# capsense-soil-sensor.net
KiCad netlist of a schematic drawn in EAGLE
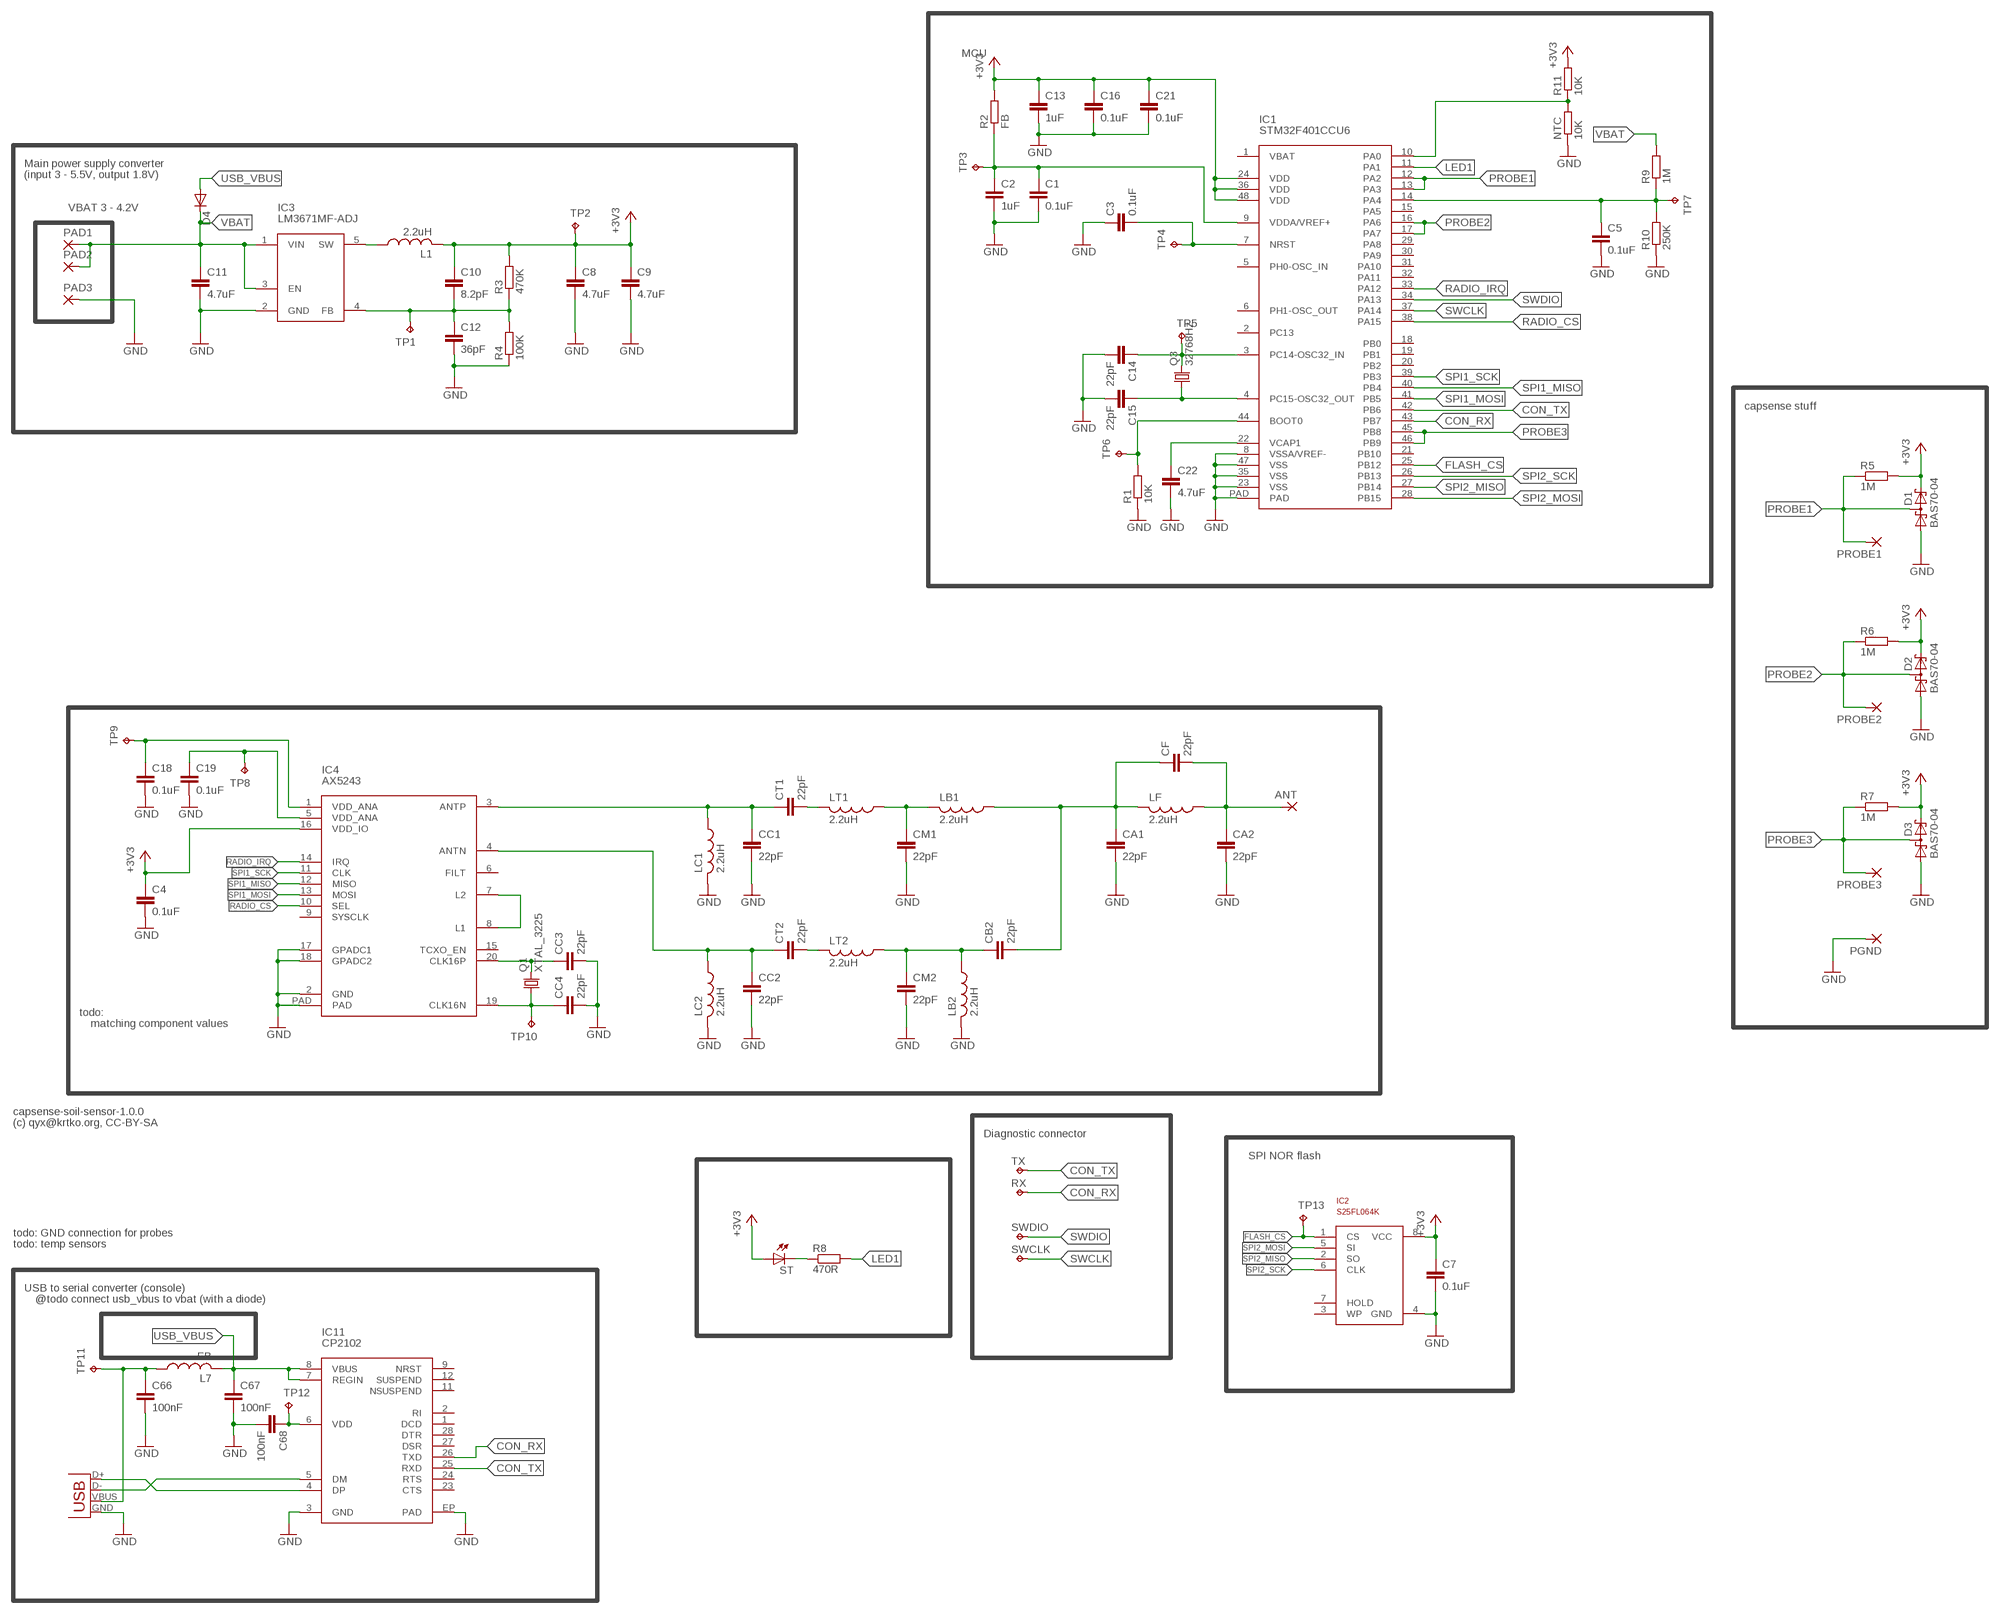
[diagram p0: schematic, sheet 1]

(export (version "E")
  (design (tool "Eeschema 10.0.6"))
  (components
    (comp (ref "ANT")
      (value "2,15/1,0")
      (footprint "eagle-import:2,15_1,0")
      (libsource (lib "eagle-import") (part "2,15/1,0"))
    )
    (comp (ref "C1")
      (value "0.1uF")
      (footprint "eagle-import:C0603")
      (libsource (lib "eagle-import") (part "C-EUC0603"))
    )
    (comp (ref "C2")
      (value "1uF")
      (footprint "eagle-import:C0603")
      (libsource (lib "eagle-import") (part "C-EUC0603"))
    )
    (comp (ref "C3")
      (value "0.1uF")
      (footprint "eagle-import:C0603")
      (libsource (lib "eagle-import") (part "C-EUC0603"))
    )
    (comp (ref "C4")
      (value "0.1uF")
      (footprint "eagle-import:C0603")
      (libsource (lib "eagle-import") (part "C-EUC0603"))
    )
    (comp (ref "C5")
      (value "0.1uF")
      (footprint "eagle-import:C0603")
      (libsource (lib "eagle-import") (part "C-EUC0603"))
    )
    (comp (ref "C7")
      (value "0.1uF")
      (footprint "eagle-import:C0603")
      (libsource (lib "eagle-import") (part "C-EUC0603"))
    )
    (comp (ref "C8")
      (value "4.7uF")
      (footprint "eagle-import:C0805")
      (libsource (lib "eagle-import") (part "C-EUC0805"))
    )
    (comp (ref "C9")
      (value "4.7uF")
      (footprint "eagle-import:C0805")
      (libsource (lib "eagle-import") (part "C-EUC0805"))
    )
    (comp (ref "C10")
      (value "8.2pF")
      (footprint "eagle-import:C0603")
      (libsource (lib "eagle-import") (part "C-EUC0603"))
    )
    (comp (ref "C11")
      (value "4.7uF")
      (footprint "eagle-import:C0805")
      (libsource (lib "eagle-import") (part "C-EUC0805"))
    )
    (comp (ref "C12")
      (value "36pF")
      (footprint "eagle-import:C0603")
      (libsource (lib "eagle-import") (part "C-EUC0603"))
    )
    (comp (ref "C13")
      (value "1uF")
      (footprint "eagle-import:C0603")
      (libsource (lib "eagle-import") (part "C-EUC0603"))
    )
    (comp (ref "C14")
      (value "22pF")
      (footprint "eagle-import:C0603")
      (libsource (lib "eagle-import") (part "C-EUC0603"))
    )
    (comp (ref "C15")
      (value "22pF")
      (footprint "eagle-import:C0603")
      (libsource (lib "eagle-import") (part "C-EUC0603"))
    )
    (comp (ref "C16")
      (value "0.1uF")
      (footprint "eagle-import:C0603")
      (libsource (lib "eagle-import") (part "C-EUC0603"))
    )
    (comp (ref "C18")
      (value "0.1uF")
      (footprint "eagle-import:C0603")
      (libsource (lib "eagle-import") (part "C-EUC0603"))
    )
    (comp (ref "C19")
      (value "0.1uF")
      (footprint "eagle-import:C0603")
      (libsource (lib "eagle-import") (part "C-EUC0603"))
    )
    (comp (ref "C21")
      (value "0.1uF")
      (footprint "eagle-import:C0603")
      (libsource (lib "eagle-import") (part "C-EUC0603"))
    )
    (comp (ref "C22")
      (value "4.7uF")
      (footprint "eagle-import:C0603")
      (libsource (lib "eagle-import") (part "C-EUC0603"))
    )
    (comp (ref "C66")
      (value "100nF")
      (footprint "eagle-import:C0603")
      (libsource (lib "eagle-import") (part "C-EUC0603"))
    )
    (comp (ref "C67")
      (value "100nF")
      (footprint "eagle-import:C0603")
      (libsource (lib "eagle-import") (part "C-EUC0603"))
    )
    (comp (ref "C68")
      (value "100nF")
      (footprint "eagle-import:C0603")
      (libsource (lib "eagle-import") (part "C-EUC0603"))
    )
    (comp (ref "CA1")
      (value "22pF")
      (footprint "eagle-import:C0603")
      (libsource (lib "eagle-import") (part "C-EUC0603"))
    )
    (comp (ref "CA2")
      (value "22pF")
      (footprint "eagle-import:C0603")
      (libsource (lib "eagle-import") (part "C-EUC0603"))
    )
    (comp (ref "CB2")
      (value "22pF")
      (footprint "eagle-import:C0603")
      (libsource (lib "eagle-import") (part "C-EUC0603"))
    )
    (comp (ref "CC1")
      (value "22pF")
      (footprint "eagle-import:C0603")
      (libsource (lib "eagle-import") (part "C-EUC0603"))
    )
    (comp (ref "CC2")
      (value "22pF")
      (footprint "eagle-import:C0603")
      (libsource (lib "eagle-import") (part "C-EUC0603"))
    )
    (comp (ref "CC3")
      (value "22pF")
      (footprint "eagle-import:C0603")
      (libsource (lib "eagle-import") (part "C-EUC0603"))
    )
    (comp (ref "CC4")
      (value "22pF")
      (footprint "eagle-import:C0603")
      (libsource (lib "eagle-import") (part "C-EUC0603"))
    )
    (comp (ref "CF")
      (value "22pF")
      (footprint "eagle-import:C0603")
      (libsource (lib "eagle-import") (part "C-EUC0603"))
    )
    (comp (ref "CM1")
      (value "22pF")
      (footprint "eagle-import:C0603")
      (libsource (lib "eagle-import") (part "C-EUC0603"))
    )
    (comp (ref "CM2")
      (value "22pF")
      (footprint "eagle-import:C0603")
      (libsource (lib "eagle-import") (part "C-EUC0603"))
    )
    (comp (ref "CT1")
      (value "22pF")
      (footprint "eagle-import:C0603")
      (libsource (lib "eagle-import") (part "C-EUC0603"))
    )
    (comp (ref "CT2")
      (value "22pF")
      (footprint "eagle-import:C0603")
      (libsource (lib "eagle-import") (part "C-EUC0603"))
    )
    (comp (ref "D1")
      (value "BAS70-04")
      (footprint "eagle-import:SOT23")
      (libsource (lib "eagle-import") (part "BAS70-04"))
    )
    (comp (ref "D2")
      (value "BAS70-04")
      (footprint "eagle-import:SOT23")
      (libsource (lib "eagle-import") (part "BAS70-04"))
    )
    (comp (ref "D3")
      (value "BAS70-04")
      (footprint "eagle-import:SOT23")
      (libsource (lib "eagle-import") (part "BAS70-04"))
    )
    (comp (ref "D4")
      (value "DIODE-SOD110-R")
      (footprint "eagle-import:SOD110-R")
      (libsource (lib "eagle-import") (part "DIODE-SOD110-R"))
    )
    (comp (ref "IC1")
      (value "STM32F401CCU6")
      (footprint "eagle-import:UFQFPN48")
      (libsource (lib "eagle-import") (part "STM32F401CCU6"))
    )
    (comp (ref "IC2")
      (value "S25FL064K")
      (footprint "eagle-import:SO-08M")
      (libsource (lib "eagle-import") (part "S25FL064K"))
    )
    (comp (ref "IC3")
      (value "LM3671MF-ADJ")
      (footprint "eagle-import:SOT23-5")
      (libsource (lib "eagle-import") (part "LM3671MF"))
    )
    (comp (ref "IC4")
      (value "AX5243")
      (footprint "eagle-import:QFN20")
      (libsource (lib "eagle-import") (part "AX5243"))
    )
    (comp (ref "IC11")
      (value "CP2102")
      (footprint "eagle-import:QFN28")
      (libsource (lib "eagle-import") (part "CP2102"))
    )
    (comp (ref "L1")
      (value "2.2uH")
      (footprint "eagle-import:L2825P")
      (libsource (lib "eagle-import") (part "L-USL2825P"))
    )
    (comp (ref "L7")
      (value "FB")
      (footprint "eagle-import:L2012C")
      (libsource (lib "eagle-import") (part "L-USL2012C"))
    )
    (comp (ref "LB1")
      (value "2.2uH")
      (footprint "eagle-import:L2012C")
      (libsource (lib "eagle-import") (part "L-USL2012C"))
    )
    (comp (ref "LB2")
      (value "2.2uH")
      (footprint "eagle-import:L2012C")
      (libsource (lib "eagle-import") (part "L-USL2012C"))
    )
    (comp (ref "LC1")
      (value "2.2uH")
      (footprint "eagle-import:L2012C")
      (libsource (lib "eagle-import") (part "L-USL2012C"))
    )
    (comp (ref "LC2")
      (value "2.2uH")
      (footprint "eagle-import:L2012C")
      (libsource (lib "eagle-import") (part "L-USL2012C"))
    )
    (comp (ref "LF")
      (value "2.2uH")
      (footprint "eagle-import:L2012C")
      (libsource (lib "eagle-import") (part "L-USL2012C"))
    )
    (comp (ref "LT1")
      (value "2.2uH")
      (footprint "eagle-import:L2012C")
      (libsource (lib "eagle-import") (part "L-USL2012C"))
    )
    (comp (ref "LT2")
      (value "2.2uH")
      (footprint "eagle-import:L2012C")
      (libsource (lib "eagle-import") (part "L-USL2012C"))
    )
    (comp (ref "NTC")
      (value "10K")
      (footprint "eagle-import:R0603")
      (libsource (lib "eagle-import") (part "R-EU_R0603"))
    )
    (comp (ref "PAD1")
      (value "SMD5")
      (footprint "eagle-import:SMD2,54-5,08")
      (libsource (lib "eagle-import") (part "SMD5"))
    )
    (comp (ref "PAD2")
      (value "SMD5")
      (footprint "eagle-import:SMD2,54-5,08")
      (libsource (lib "eagle-import") (part "SMD5"))
    )
    (comp (ref "PAD3")
      (value "2,15/1,0")
      (footprint "eagle-import:2,15_1,0")
      (libsource (lib "eagle-import") (part "2,15/1,0"))
    )
    (comp (ref "PGND")
      (value "2,15/1,0")
      (footprint "eagle-import:2,15_1,0")
      (libsource (lib "eagle-import") (part "2,15/1,0"))
    )
    (comp (ref "PROBE1")
      (value "2,15/1,0")
      (footprint "eagle-import:2,15_1,0")
      (libsource (lib "eagle-import") (part "2,15/1,0"))
    )
    (comp (ref "PROBE2")
      (value "2,15/1,0")
      (footprint "eagle-import:2,15_1,0")
      (libsource (lib "eagle-import") (part "2,15/1,0"))
    )
    (comp (ref "PROBE3")
      (value "2,15/1,0")
      (footprint "eagle-import:2,15_1,0")
      (libsource (lib "eagle-import") (part "2,15/1,0"))
    )
    (comp (ref "Q1")
      (value "XTAL_3225")
      (footprint "eagle-import:XTAL_3225")
      (libsource (lib "eagle-import") (part "XTAL_3225"))
    )
    (comp (ref "Q3")
      (value "32768Hz")
      (footprint "eagle-import:TC26H")
      (libsource (lib "eagle-import") (part "CRYSTALTC26H"))
    )
    (comp (ref "R1")
      (value "10K")
      (footprint "eagle-import:R0603")
      (libsource (lib "eagle-import") (part "R-EU_R0603"))
    )
    (comp (ref "R2")
      (value "FB")
      (footprint "eagle-import:R0603")
      (libsource (lib "eagle-import") (part "R-EU_R0603"))
    )
    (comp (ref "R3")
      (value "470K")
      (footprint "eagle-import:R0603")
      (libsource (lib "eagle-import") (part "R-EU_R0603"))
    )
    (comp (ref "R4")
      (value "100K")
      (footprint "eagle-import:R0603")
      (libsource (lib "eagle-import") (part "R-EU_R0603"))
    )
    (comp (ref "R5")
      (value "1M")
      (footprint "eagle-import:R0603")
      (libsource (lib "eagle-import") (part "R-EU_R0603"))
    )
    (comp (ref "R6")
      (value "1M")
      (footprint "eagle-import:R0603")
      (libsource (lib "eagle-import") (part "R-EU_R0603"))
    )
    (comp (ref "R7")
      (value "1M")
      (footprint "eagle-import:R0603")
      (libsource (lib "eagle-import") (part "R-EU_R0603"))
    )
    (comp (ref "R8")
      (value "470R")
      (footprint "eagle-import:R0603")
      (libsource (lib "eagle-import") (part "R-EU_R0603"))
    )
    (comp (ref "R9")
      (value "1M")
      (footprint "eagle-import:R0603")
      (libsource (lib "eagle-import") (part "R-EU_R0603"))
    )
    (comp (ref "R10")
      (value "250K")
      (footprint "eagle-import:R0603")
      (libsource (lib "eagle-import") (part "R-EU_R0603"))
    )
    (comp (ref "R11")
      (value "10K")
      (footprint "eagle-import:R0603")
      (libsource (lib "eagle-import") (part "R-EU_R0603"))
    )
    (comp (ref "RX")
      (value "TPB2,54")
      (footprint "eagle-import:B2,54")
      (libsource (lib "eagle-import") (part "TPB2,54"))
    )
    (comp (ref "ST")
      (value "LEDCHIPLED_0603")
      (footprint "eagle-import:CHIPLED_0603")
      (libsource (lib "eagle-import") (part "LEDCHIPLED_0603"))
    )
    (comp (ref "SWCLK")
      (value "TPB2,54")
      (footprint "eagle-import:B2,54")
      (libsource (lib "eagle-import") (part "TPB2,54"))
    )
    (comp (ref "SWDIO")
      (value "TPB2,54")
      (footprint "eagle-import:B2,54")
      (libsource (lib "eagle-import") (part "TPB2,54"))
    )
    (comp (ref "TP1")
      (value "TPB1,27")
      (footprint "eagle-import:B1,27")
      (libsource (lib "eagle-import") (part "TPB1,27"))
    )
    (comp (ref "TP2")
      (value "TPB1,27")
      (footprint "eagle-import:B1,27")
      (libsource (lib "eagle-import") (part "TPB1,27"))
    )
    (comp (ref "TP3")
      (value "TPB1,27")
      (footprint "eagle-import:B1,27")
      (libsource (lib "eagle-import") (part "TPB1,27"))
    )
    (comp (ref "TP4")
      (value "TPB1,27")
      (footprint "eagle-import:B1,27")
      (libsource (lib "eagle-import") (part "TPB1,27"))
    )
    (comp (ref "TP5")
      (value "TPB1,27")
      (footprint "eagle-import:B1,27")
      (libsource (lib "eagle-import") (part "TPB1,27"))
    )
    (comp (ref "TP6")
      (value "TPB1,27")
      (footprint "eagle-import:B1,27")
      (libsource (lib "eagle-import") (part "TPB1,27"))
    )
    (comp (ref "TP7")
      (value "TPB1,27")
      (footprint "eagle-import:B1,27")
      (libsource (lib "eagle-import") (part "TPB1,27"))
    )
    (comp (ref "TP8")
      (value "TPB1,27")
      (footprint "eagle-import:B1,27")
      (libsource (lib "eagle-import") (part "TPB1,27"))
    )
    (comp (ref "TP9")
      (value "TPB1,27")
      (footprint "eagle-import:B1,27")
      (libsource (lib "eagle-import") (part "TPB1,27"))
    )
    (comp (ref "TP10")
      (value "TPB1,27")
      (footprint "eagle-import:B1,27")
      (libsource (lib "eagle-import") (part "TPB1,27"))
    )
    (comp (ref "TP11")
      (value "TPB1,27")
      (footprint "eagle-import:B1,27")
      (libsource (lib "eagle-import") (part "TPB1,27"))
    )
    (comp (ref "TP12")
      (value "TPB1,27")
      (footprint "eagle-import:B1,27")
      (libsource (lib "eagle-import") (part "TPB1,27"))
    )
    (comp (ref "TP13")
      (value "TPB1,27")
      (footprint "eagle-import:B1,27")
      (libsource (lib "eagle-import") (part "TPB1,27"))
    )
    (comp (ref "TX")
      (value "TPB2,54")
      (footprint "eagle-import:B2,54")
      (libsource (lib "eagle-import") (part "TPB2,54"))
    )
    (comp (ref "X5")
      (value "USB-MICROB")
      (footprint "eagle-import:USB-MICROB")
      (libsource (lib "eagle-import") (part "USB-MICROB"))
    )
  )
  (nets
    (net (code "1") (name "+3V3") (class "Default")
      (node (ref "C10") (pin "1") (pinfunction "1_1") (pintype "passive"))
      (node (ref "C13") (pin "1") (pinfunction "1_1") (pintype "passive"))
      (node (ref "C16") (pin "1") (pinfunction "1_1") (pintype "passive"))
      (node (ref "C21") (pin "1") (pinfunction "1_1") (pintype "passive"))
      (node (ref "C4") (pin "1") (pinfunction "1_1") (pintype "passive"))
      (node (ref "C7") (pin "1") (pinfunction "1_1") (pintype "passive"))
      (node (ref "C8") (pin "1") (pinfunction "1_1") (pintype "passive"))
      (node (ref "C9") (pin "1") (pinfunction "1_1") (pintype "passive"))
      (node (ref "D1") (pin "2") (pinfunction "C2_2") (pintype "passive"))
      (node (ref "D2") (pin "2") (pinfunction "C2_2") (pintype "passive"))
      (node (ref "D3") (pin "2") (pinfunction "C2_2") (pintype "passive"))
      (node (ref "IC1") (pin "24") (pinfunction "VDD_24") (pintype "bidirectional"))
      (node (ref "IC1") (pin "36") (pinfunction "VDD_36") (pintype "bidirectional"))
      (node (ref "IC1") (pin "48") (pinfunction "VDD_48") (pintype "bidirectional"))
      (node (ref "IC2") (pin "8") (pinfunction "VCC_8") (pintype "power_in"))
      (node (ref "IC4") (pin "16") (pinfunction "VDD_IO_16") (pintype "bidirectional"))
      (node (ref "L1") (pin "2") (pinfunction "2_2") (pintype "passive"))
      (node (ref "R11") (pin "2") (pinfunction "2_2") (pintype "passive"))
      (node (ref "R2") (pin "2") (pinfunction "2_2") (pintype "passive"))
      (node (ref "R3") (pin "2") (pinfunction "2_2") (pintype "passive"))
      (node (ref "R5") (pin "2") (pinfunction "2_2") (pintype "passive"))
      (node (ref "R6") (pin "2") (pinfunction "2_2") (pintype "passive"))
      (node (ref "R7") (pin "2") (pinfunction "2_2") (pintype "passive"))
      (node (ref "ST") (pin "A") (pinfunction "A_A") (pintype "passive"))
      (node (ref "TP2") (pin "TP") (pinfunction "TP_TP") (pintype "input"))
    )
    (net (code "2") (name "CON_RX") (class "Default")
      (node (ref "IC1") (pin "43") (pinfunction "PB7_43") (pintype "bidirectional"))
      (node (ref "IC11") (pin "26") (pinfunction "TXD_26") (pintype "bidirectional"))
      (node (ref "RX") (pin "TP") (pinfunction "TP_TP") (pintype "input"))
    )
    (net (code "3") (name "CON_TX") (class "Default")
      (node (ref "IC1") (pin "42") (pinfunction "PB6_42") (pintype "bidirectional"))
      (node (ref "IC11") (pin "25") (pinfunction "RXD_25") (pintype "bidirectional"))
      (node (ref "TX") (pin "TP") (pinfunction "TP_TP") (pintype "input"))
    )
    (net (code "4") (name "FLASH_CS") (class "Default")
      (node (ref "IC1") (pin "25") (pinfunction "PB12_25") (pintype "bidirectional"))
      (node (ref "IC2") (pin "1") (pinfunction "CS_1") (pintype "bidirectional"))
      (node (ref "TP13") (pin "TP") (pinfunction "TP_TP") (pintype "input"))
    )
    (net (code "5") (name "GND") (class "Default")
      (node (ref "C1") (pin "2") (pinfunction "2_2") (pintype "passive"))
      (node (ref "C11") (pin "2") (pinfunction "2_2") (pintype "passive"))
      (node (ref "C12") (pin "2") (pinfunction "2_2") (pintype "passive"))
      (node (ref "C13") (pin "2") (pinfunction "2_2") (pintype "passive"))
      (node (ref "C14") (pin "2") (pinfunction "2_2") (pintype "passive"))
      (node (ref "C15") (pin "2") (pinfunction "2_2") (pintype "passive"))
      (node (ref "C16") (pin "2") (pinfunction "2_2") (pintype "passive"))
      (node (ref "C18") (pin "2") (pinfunction "2_2") (pintype "passive"))
      (node (ref "C19") (pin "2") (pinfunction "2_2") (pintype "passive"))
      (node (ref "C2") (pin "2") (pinfunction "2_2") (pintype "passive"))
      (node (ref "C21") (pin "2") (pinfunction "2_2") (pintype "passive"))
      (node (ref "C22") (pin "2") (pinfunction "2_2") (pintype "passive"))
      (node (ref "C3") (pin "1") (pinfunction "1_1") (pintype "passive"))
      (node (ref "C4") (pin "2") (pinfunction "2_2") (pintype "passive"))
      (node (ref "C5") (pin "2") (pinfunction "2_2") (pintype "passive"))
      (node (ref "C66") (pin "2") (pinfunction "2_2") (pintype "passive"))
      (node (ref "C67") (pin "2") (pinfunction "2_2") (pintype "passive"))
      (node (ref "C68") (pin "2") (pinfunction "2_2") (pintype "passive"))
      (node (ref "C7") (pin "2") (pinfunction "2_2") (pintype "passive"))
      (node (ref "C8") (pin "2") (pinfunction "2_2") (pintype "passive"))
      (node (ref "C9") (pin "2") (pinfunction "2_2") (pintype "passive"))
      (node (ref "CA1") (pin "2") (pinfunction "2_2") (pintype "passive"))
      (node (ref "CA2") (pin "2") (pinfunction "2_2") (pintype "passive"))
      (node (ref "CC1") (pin "2") (pinfunction "2_2") (pintype "passive"))
      (node (ref "CC2") (pin "2") (pinfunction "2_2") (pintype "passive"))
      (node (ref "CC3") (pin "2") (pinfunction "2_2") (pintype "passive"))
      (node (ref "CC4") (pin "2") (pinfunction "2_2") (pintype "passive"))
      (node (ref "CM1") (pin "2") (pinfunction "2_2") (pintype "passive"))
      (node (ref "CM2") (pin "2") (pinfunction "2_2") (pintype "passive"))
      (node (ref "D1") (pin "1") (pinfunction "A1_1") (pintype "passive"))
      (node (ref "D2") (pin "1") (pinfunction "A1_1") (pintype "passive"))
      (node (ref "D3") (pin "1") (pinfunction "A1_1") (pintype "passive"))
      (node (ref "IC1") (pin "23") (pinfunction "VSS_23") (pintype "bidirectional"))
      (node (ref "IC1") (pin "35") (pinfunction "VSS_35") (pintype "bidirectional"))
      (node (ref "IC1") (pin "47") (pinfunction "VSS_47") (pintype "bidirectional"))
      (node (ref "IC1") (pin "8") (pinfunction "VSSA/VREF-_8") (pintype "bidirectional"))
      (node (ref "IC1") (pin "PAD") (pinfunction "PAD_PAD") (pintype "bidirectional"))
      (node (ref "IC11") (pin "3") (pinfunction "GND_3") (pintype "bidirectional"))
      (node (ref "IC11") (pin "EP") (pinfunction "PAD_EP") (pintype "bidirectional"))
      (node (ref "IC2") (pin "4") (pinfunction "GND_4") (pintype "power_in"))
      (node (ref "IC3") (pin "2") (pinfunction "GND_2") (pintype "bidirectional"))
      (node (ref "IC4") (pin "17") (pinfunction "GPADC1_17") (pintype "bidirectional"))
      (node (ref "IC4") (pin "18") (pinfunction "GPADC2_18") (pintype "bidirectional"))
      (node (ref "IC4") (pin "2") (pinfunction "GND_2") (pintype "bidirectional"))
      (node (ref "IC4") (pin "PAD") (pinfunction "PAD_PAD") (pintype "bidirectional"))
      (node (ref "LB2") (pin "2") (pinfunction "2_2") (pintype "passive"))
      (node (ref "LC1") (pin "2") (pinfunction "2_2") (pintype "passive"))
      (node (ref "LC2") (pin "2") (pinfunction "2_2") (pintype "passive"))
      (node (ref "NTC") (pin "1") (pinfunction "1_1") (pintype "passive"))
      (node (ref "PAD3") (pin "1") (pinfunction "P_1") (pintype "passive"))
      (node (ref "PGND") (pin "1") (pinfunction "P_1") (pintype "passive"))
      (node (ref "R1") (pin "1") (pinfunction "1_1") (pintype "passive"))
      (node (ref "R10") (pin "1") (pinfunction "1_1") (pintype "passive"))
      (node (ref "R4") (pin "1") (pinfunction "1_1") (pintype "passive"))
      (node (ref "X5") (pin "GND") (pinfunction "GND_GND") (pintype "bidirectional"))
    )
    (net (code "6") (name "LED1") (class "Default")
      (node (ref "IC1") (pin "11") (pinfunction "PA1_11") (pintype "bidirectional"))
      (node (ref "R8") (pin "2") (pinfunction "2_2") (pintype "passive"))
    )
    (net (code "7") (name "Net-(ANT-P)") (class "Default")
      (node (ref "ANT") (pin "1") (pinfunction "P_1") (pintype "passive"))
      (node (ref "CA2") (pin "1") (pinfunction "1_1") (pintype "passive"))
      (node (ref "CF") (pin "2") (pinfunction "2_2") (pintype "passive"))
      (node (ref "LF") (pin "1") (pinfunction "1_1") (pintype "passive"))
    )
    (net (code "8") (name "Net-(C18-Pad1)") (class "Default")
      (node (ref "C18") (pin "1") (pinfunction "1_1") (pintype "passive"))
      (node (ref "IC4") (pin "1") (pinfunction "VDD_ANA_1") (pintype "bidirectional"))
      (node (ref "TP9") (pin "TP") (pinfunction "TP_TP") (pintype "input"))
    )
    (net (code "9") (name "Net-(C19-Pad1)") (class "Default")
      (node (ref "C19") (pin "1") (pinfunction "1_1") (pintype "passive"))
      (node (ref "IC4") (pin "5") (pinfunction "VDD_ANA_5") (pintype "bidirectional"))
      (node (ref "TP8") (pin "TP") (pinfunction "TP_TP") (pintype "input"))
    )
    (net (code "10") (name "Net-(C66-Pad1)") (class "Default")
      (node (ref "C66") (pin "1") (pinfunction "1_1") (pintype "passive"))
      (node (ref "L7") (pin "1") (pinfunction "1_1") (pintype "passive"))
      (node (ref "TP11") (pin "TP") (pinfunction "TP_TP") (pintype "input"))
      (node (ref "X5") (pin "VBUS") (pinfunction "VBUS_VBUS") (pintype "bidirectional"))
    )
    (net (code "11") (name "Net-(CA1-Pad1)") (class "Default")
      (node (ref "CA1") (pin "1") (pinfunction "1_1") (pintype "passive"))
      (node (ref "CB2") (pin "2") (pinfunction "2_2") (pintype "passive"))
      (node (ref "CF") (pin "1") (pinfunction "1_1") (pintype "passive"))
      (node (ref "LB1") (pin "1") (pinfunction "1_1") (pintype "passive"))
      (node (ref "LF") (pin "2") (pinfunction "2_2") (pintype "passive"))
    )
    (net (code "12") (name "Net-(CB2-Pad1)") (class "Default")
      (node (ref "CB2") (pin "1") (pinfunction "1_1") (pintype "passive"))
      (node (ref "CM2") (pin "1") (pinfunction "1_1") (pintype "passive"))
      (node (ref "LB2") (pin "1") (pinfunction "1_1") (pintype "passive"))
      (node (ref "LT2") (pin "1") (pinfunction "1_1") (pintype "passive"))
    )
    (net (code "13") (name "Net-(CM1-Pad1)") (class "Default")
      (node (ref "CM1") (pin "1") (pinfunction "1_1") (pintype "passive"))
      (node (ref "LB1") (pin "2") (pinfunction "2_2") (pintype "passive"))
      (node (ref "LT1") (pin "1") (pinfunction "1_1") (pintype "passive"))
    )
    (net (code "14") (name "Net-(CT1-Pad2)") (class "Default")
      (node (ref "CT1") (pin "2") (pinfunction "2_2") (pintype "passive"))
      (node (ref "LT1") (pin "2") (pinfunction "2_2") (pintype "passive"))
    )
    (net (code "15") (name "Net-(CT2-Pad2)") (class "Default")
      (node (ref "CT2") (pin "2") (pinfunction "2_2") (pintype "passive"))
      (node (ref "LT2") (pin "2") (pinfunction "2_2") (pintype "passive"))
    )
    (net (code "16") (name "Net-(IC1-BOOT0)") (class "Default")
      (node (ref "IC1") (pin "44") (pinfunction "BOOT0_44") (pintype "bidirectional"))
      (node (ref "R1") (pin "2") (pinfunction "2_2") (pintype "passive"))
      (node (ref "TP6") (pin "TP") (pinfunction "TP_TP") (pintype "input"))
    )
    (net (code "17") (name "Net-(IC1-NRST)") (class "Default")
      (node (ref "C3") (pin "2") (pinfunction "2_2") (pintype "passive"))
      (node (ref "IC1") (pin "7") (pinfunction "NRST_7") (pintype "bidirectional"))
      (node (ref "TP4") (pin "TP") (pinfunction "TP_TP") (pintype "input"))
    )
    (net (code "18") (name "Net-(IC1-PA0)") (class "Default")
      (node (ref "IC1") (pin "10") (pinfunction "PA0_10") (pintype "bidirectional"))
      (node (ref "NTC") (pin "2") (pinfunction "2_2") (pintype "passive"))
      (node (ref "R11") (pin "1") (pinfunction "1_1") (pintype "passive"))
    )
    (net (code "19") (name "Net-(IC1-PA4)") (class "Default")
      (node (ref "C5") (pin "1") (pinfunction "1_1") (pintype "passive"))
      (node (ref "IC1") (pin "14") (pinfunction "PA4_14") (pintype "bidirectional"))
      (node (ref "R10") (pin "2") (pinfunction "2_2") (pintype "passive"))
      (node (ref "R9") (pin "1") (pinfunction "1_1") (pintype "passive"))
      (node (ref "TP7") (pin "TP") (pinfunction "TP_TP") (pintype "input"))
    )
    (net (code "20") (name "Net-(IC1-PC14-OSC32_IN)") (class "Default")
      (node (ref "C14") (pin "1") (pinfunction "1_1") (pintype "passive"))
      (node (ref "IC1") (pin "3") (pinfunction "PC14-OSC32_IN_3") (pintype "bidirectional"))
      (node (ref "Q3") (pin "2") (pinfunction "2_2") (pintype "passive"))
      (node (ref "TP5") (pin "TP") (pinfunction "TP_TP") (pintype "input"))
    )
    (net (code "21") (name "Net-(IC1-PC15-OSC32_OUT)") (class "Default")
      (node (ref "C15") (pin "1") (pinfunction "1_1") (pintype "passive"))
      (node (ref "IC1") (pin "4") (pinfunction "PC15-OSC32_OUT_4") (pintype "bidirectional"))
      (node (ref "Q3") (pin "1") (pinfunction "1_1") (pintype "passive"))
    )
    (net (code "22") (name "Net-(IC1-VCAP1)") (class "Default")
      (node (ref "C22") (pin "1") (pinfunction "1_1") (pintype "passive"))
      (node (ref "IC1") (pin "22") (pinfunction "VCAP1_22") (pintype "bidirectional"))
    )
    (net (code "23") (name "Net-(IC1-VDDA{slash}VREF+)") (class "Default")
      (node (ref "C1") (pin "1") (pinfunction "1_1") (pintype "passive"))
      (node (ref "C2") (pin "1") (pinfunction "1_1") (pintype "passive"))
      (node (ref "IC1") (pin "9") (pinfunction "VDDA/VREF+_9") (pintype "bidirectional"))
      (node (ref "R2") (pin "1") (pinfunction "1_1") (pintype "passive"))
      (node (ref "TP3") (pin "TP") (pinfunction "TP_TP") (pintype "input"))
    )
    (net (code "24") (name "Net-(IC3-FB)") (class "Default")
      (node (ref "C10") (pin "2") (pinfunction "2_2") (pintype "passive"))
      (node (ref "C12") (pin "1") (pinfunction "1_1") (pintype "passive"))
      (node (ref "IC3") (pin "4") (pinfunction "FB_4") (pintype "bidirectional"))
      (node (ref "R3") (pin "1") (pinfunction "1_1") (pintype "passive"))
      (node (ref "R4") (pin "2") (pinfunction "2_2") (pintype "passive"))
      (node (ref "TP1") (pin "TP") (pinfunction "TP_TP") (pintype "input"))
    )
    (net (code "25") (name "Net-(IC3-SW)") (class "Default")
      (node (ref "IC3") (pin "5") (pinfunction "SW_5") (pintype "bidirectional"))
      (node (ref "L1") (pin "1") (pinfunction "1_1") (pintype "passive"))
    )
    (net (code "26") (name "Net-(IC4-ANTN)") (class "Default")
      (node (ref "CC2") (pin "1") (pinfunction "1_1") (pintype "passive"))
      (node (ref "CT2") (pin "1") (pinfunction "1_1") (pintype "passive"))
      (node (ref "IC4") (pin "4") (pinfunction "ANTN_4") (pintype "bidirectional"))
      (node (ref "LC2") (pin "1") (pinfunction "1_1") (pintype "passive"))
    )
    (net (code "27") (name "Net-(IC4-ANTP)") (class "Default")
      (node (ref "CC1") (pin "1") (pinfunction "1_1") (pintype "passive"))
      (node (ref "CT1") (pin "1") (pinfunction "1_1") (pintype "passive"))
      (node (ref "IC4") (pin "3") (pinfunction "ANTP_3") (pintype "bidirectional"))
      (node (ref "LC1") (pin "1") (pinfunction "1_1") (pintype "passive"))
    )
    (net (code "28") (name "Net-(IC4-CLK16N)") (class "Default")
      (node (ref "CC4") (pin "1") (pinfunction "1_1") (pintype "passive"))
      (node (ref "IC4") (pin "19") (pinfunction "CLK16N_19") (pintype "bidirectional"))
      (node (ref "Q1") (pin "1") (pinfunction "1_1") (pintype "passive"))
      (node (ref "TP10") (pin "TP") (pinfunction "TP_TP") (pintype "input"))
    )
    (net (code "29") (name "Net-(IC4-CLK16P)") (class "Default")
      (node (ref "CC3") (pin "1") (pinfunction "1_1") (pintype "passive"))
      (node (ref "IC4") (pin "20") (pinfunction "CLK16P_20") (pintype "bidirectional"))
      (node (ref "Q1") (pin "3") (pinfunction "2_3") (pintype "passive"))
    )
    (net (code "30") (name "Net-(IC4-L1)") (class "Default")
      (node (ref "IC4") (pin "7") (pinfunction "L2_7") (pintype "bidirectional"))
      (node (ref "IC4") (pin "8") (pinfunction "L1_8") (pintype "bidirectional"))
    )
    (net (code "31") (name "Net-(IC11-DM)") (class "Default")
      (node (ref "IC11") (pin "5") (pinfunction "DM_5") (pintype "bidirectional"))
      (node (ref "X5") (pin "D-") (pinfunction "D-_D-") (pintype "bidirectional"))
    )
    (net (code "32") (name "Net-(IC11-DP)") (class "Default")
      (node (ref "IC11") (pin "4") (pinfunction "DP_4") (pintype "bidirectional"))
      (node (ref "X5") (pin "D+") (pinfunction "D+_D+") (pintype "bidirectional"))
    )
    (net (code "33") (name "Net-(IC11-VDD)") (class "Default")
      (node (ref "C68") (pin "1") (pinfunction "1_1") (pintype "passive"))
      (node (ref "IC11") (pin "6") (pinfunction "VDD_6") (pintype "bidirectional"))
      (node (ref "TP12") (pin "TP") (pinfunction "TP_TP") (pintype "input"))
    )
    (net (code "34") (name "Net-(R8-Pad1)") (class "Default")
      (node (ref "R8") (pin "1") (pinfunction "1_1") (pintype "passive"))
      (node (ref "ST") (pin "C") (pinfunction "C_C") (pintype "passive"))
    )
    (net (code "35") (name "PROBE1") (class "Default")
      (node (ref "D1") (pin "3") (pinfunction "C1A2_3") (pintype "passive"))
      (node (ref "IC1") (pin "12") (pinfunction "PA2_12") (pintype "bidirectional"))
      (node (ref "IC1") (pin "13") (pinfunction "PA3_13") (pintype "bidirectional"))
      (node (ref "PROBE1") (pin "1") (pinfunction "P_1") (pintype "passive"))
      (node (ref "R5") (pin "1") (pinfunction "1_1") (pintype "passive"))
    )
    (net (code "36") (name "PROBE2") (class "Default")
      (node (ref "D2") (pin "3") (pinfunction "C1A2_3") (pintype "passive"))
      (node (ref "IC1") (pin "16") (pinfunction "PA6_16") (pintype "bidirectional"))
      (node (ref "IC1") (pin "17") (pinfunction "PA7_17") (pintype "bidirectional"))
      (node (ref "PROBE2") (pin "1") (pinfunction "P_1") (pintype "passive"))
      (node (ref "R6") (pin "1") (pinfunction "1_1") (pintype "passive"))
    )
    (net (code "37") (name "PROBE3") (class "Default")
      (node (ref "D3") (pin "3") (pinfunction "C1A2_3") (pintype "passive"))
      (node (ref "IC1") (pin "45") (pinfunction "PB8_45") (pintype "bidirectional"))
      (node (ref "IC1") (pin "46") (pinfunction "PB9_46") (pintype "bidirectional"))
      (node (ref "PROBE3") (pin "1") (pinfunction "P_1") (pintype "passive"))
      (node (ref "R7") (pin "1") (pinfunction "1_1") (pintype "passive"))
    )
    (net (code "38") (name "RADIO_CS") (class "Default")
      (node (ref "IC1") (pin "38") (pinfunction "PA15_38") (pintype "bidirectional"))
      (node (ref "IC4") (pin "10") (pinfunction "SEL_10") (pintype "bidirectional"))
    )
    (net (code "39") (name "RADIO_IRQ") (class "Default")
      (node (ref "IC1") (pin "33") (pinfunction "PA12_33") (pintype "bidirectional"))
      (node (ref "IC4") (pin "14") (pinfunction "IRQ_14") (pintype "bidirectional"))
    )
    (net (code "40") (name "SPI1_MISO") (class "Default")
      (node (ref "IC1") (pin "40") (pinfunction "PB4_40") (pintype "bidirectional"))
      (node (ref "IC4") (pin "12") (pinfunction "MISO_12") (pintype "bidirectional"))
    )
    (net (code "41") (name "SPI1_MOSI") (class "Default")
      (node (ref "IC1") (pin "41") (pinfunction "PB5_41") (pintype "bidirectional"))
      (node (ref "IC4") (pin "13") (pinfunction "MOSI_13") (pintype "bidirectional"))
    )
    (net (code "42") (name "SPI1_SCK") (class "Default")
      (node (ref "IC1") (pin "39") (pinfunction "PB3_39") (pintype "bidirectional"))
      (node (ref "IC4") (pin "11") (pinfunction "CLK_11") (pintype "bidirectional"))
    )
    (net (code "43") (name "SPI2_MISO") (class "Default")
      (node (ref "IC1") (pin "27") (pinfunction "PB14_27") (pintype "bidirectional"))
      (node (ref "IC2") (pin "2") (pinfunction "SO_2") (pintype "bidirectional"))
    )
    (net (code "44") (name "SPI2_MOSI") (class "Default")
      (node (ref "IC1") (pin "28") (pinfunction "PB15_28") (pintype "bidirectional"))
      (node (ref "IC2") (pin "5") (pinfunction "SI_5") (pintype "bidirectional"))
    )
    (net (code "45") (name "SPI2_SCK") (class "Default")
      (node (ref "IC1") (pin "26") (pinfunction "PB13_26") (pintype "bidirectional"))
      (node (ref "IC2") (pin "6") (pinfunction "CLK_6") (pintype "bidirectional"))
    )
    (net (code "46") (name "SWCLK") (class "Default")
      (node (ref "IC1") (pin "37") (pinfunction "PA14_37") (pintype "bidirectional"))
      (node (ref "SWCLK") (pin "TP") (pinfunction "TP_TP") (pintype "input"))
    )
    (net (code "47") (name "SWDIO") (class "Default")
      (node (ref "IC1") (pin "34") (pinfunction "PA13_34") (pintype "bidirectional"))
      (node (ref "SWDIO") (pin "TP") (pinfunction "TP_TP") (pintype "input"))
    )
    (net (code "48") (name "USB_VBUS") (class "Default")
      (node (ref "C67") (pin "1") (pinfunction "1_1") (pintype "passive"))
      (node (ref "D4") (pin "A") (pinfunction "A_A") (pintype "passive"))
      (node (ref "IC11") (pin "7") (pinfunction "REGIN_7") (pintype "bidirectional"))
      (node (ref "IC11") (pin "8") (pinfunction "VBUS_8") (pintype "bidirectional"))
      (node (ref "L7") (pin "2") (pinfunction "2_2") (pintype "passive"))
    )
    (net (code "49") (name "VBAT") (class "Default")
      (node (ref "C11") (pin "1") (pinfunction "1_1") (pintype "passive"))
      (node (ref "D4") (pin "C") (pinfunction "C_C") (pintype "passive"))
      (node (ref "IC3") (pin "1") (pinfunction "VIN_1") (pintype "bidirectional"))
      (node (ref "IC3") (pin "3") (pinfunction "EN_3") (pintype "bidirectional"))
      (node (ref "PAD1") (pin "1") (pinfunction "P_1") (pintype "passive"))
      (node (ref "PAD2") (pin "1") (pinfunction "P_1") (pintype "passive"))
      (node (ref "R9") (pin "2") (pinfunction "2_2") (pintype "passive"))
    )
    (net (code "50") (name "unconnected-(IC1-PA5-Pad15)") (class "Default")
      (node (ref "IC1") (pin "15") (pinfunction "PA5_15") (pintype "bidirectional"))
    )
    (net (code "51") (name "unconnected-(IC1-PA8-Pad29)") (class "Default")
      (node (ref "IC1") (pin "29") (pinfunction "PA8_29") (pintype "bidirectional"))
    )
    (net (code "52") (name "unconnected-(IC1-PA9-Pad30)") (class "Default")
      (node (ref "IC1") (pin "30") (pinfunction "PA9_30") (pintype "bidirectional"))
    )
    (net (code "53") (name "unconnected-(IC1-PA10-Pad31)") (class "Default")
      (node (ref "IC1") (pin "31") (pinfunction "PA10_31") (pintype "bidirectional"))
    )
    (net (code "54") (name "unconnected-(IC1-PA11-Pad32)") (class "Default")
      (node (ref "IC1") (pin "32") (pinfunction "PA11_32") (pintype "bidirectional"))
    )
    (net (code "55") (name "unconnected-(IC1-PB0-Pad18)") (class "Default")
      (node (ref "IC1") (pin "18") (pinfunction "PB0_18") (pintype "bidirectional"))
    )
    (net (code "56") (name "unconnected-(IC1-PB1-Pad19)") (class "Default")
      (node (ref "IC1") (pin "19") (pinfunction "PB1_19") (pintype "bidirectional"))
    )
    (net (code "57") (name "unconnected-(IC1-PB2-Pad20)") (class "Default")
      (node (ref "IC1") (pin "20") (pinfunction "PB2_20") (pintype "bidirectional"))
    )
    (net (code "58") (name "unconnected-(IC1-PB10-Pad21)") (class "Default")
      (node (ref "IC1") (pin "21") (pinfunction "PB10_21") (pintype "bidirectional"))
    )
    (net (code "59") (name "unconnected-(IC1-PC13-Pad2)") (class "Default")
      (node (ref "IC1") (pin "2") (pinfunction "PC13_2") (pintype "bidirectional"))
    )
    (net (code "60") (name "unconnected-(IC1-PH0-OSC_IN-Pad5)") (class "Default")
      (node (ref "IC1") (pin "5") (pinfunction "PH0-OSC_IN_5") (pintype "bidirectional"))
    )
    (net (code "61") (name "unconnected-(IC1-PH1-OSC_OUT-Pad6)") (class "Default")
      (node (ref "IC1") (pin "6") (pinfunction "PH1-OSC_OUT_6") (pintype "bidirectional"))
    )
    (net (code "62") (name "unconnected-(IC1-VBAT-Pad1)") (class "Default")
      (node (ref "IC1") (pin "1") (pinfunction "VBAT_1") (pintype "bidirectional"))
    )
    (net (code "63") (name "unconnected-(IC2-HOLD-Pad7)") (class "Default")
      (node (ref "IC2") (pin "7") (pinfunction "HOLD_7") (pintype "bidirectional"))
    )
    (net (code "64") (name "unconnected-(IC2-WP-Pad3)") (class "Default")
      (node (ref "IC2") (pin "3") (pinfunction "WP_3") (pintype "bidirectional"))
    )
    (net (code "65") (name "unconnected-(IC4-FILT-Pad6)") (class "Default")
      (node (ref "IC4") (pin "6") (pinfunction "FILT_6") (pintype "bidirectional"))
    )
    (net (code "66") (name "unconnected-(IC4-SYSCLK-Pad9)") (class "Default")
      (node (ref "IC4") (pin "9") (pinfunction "SYSCLK_9") (pintype "bidirectional"))
    )
    (net (code "67") (name "unconnected-(IC4-TCXO_EN-Pad15)") (class "Default")
      (node (ref "IC4") (pin "15") (pinfunction "TCXO_EN_15") (pintype "bidirectional"))
    )
    (net (code "68") (name "unconnected-(IC11-CTS-Pad23)") (class "Default")
      (node (ref "IC11") (pin "23") (pinfunction "CTS_23") (pintype "bidirectional"))
    )
    (net (code "69") (name "unconnected-(IC11-DCD-Pad1)") (class "Default")
      (node (ref "IC11") (pin "1") (pinfunction "DCD_1") (pintype "bidirectional"))
    )
    (net (code "70") (name "unconnected-(IC11-DSR-Pad27)") (class "Default")
      (node (ref "IC11") (pin "27") (pinfunction "DSR_27") (pintype "bidirectional"))
    )
    (net (code "71") (name "unconnected-(IC11-DTR-Pad28)") (class "Default")
      (node (ref "IC11") (pin "28") (pinfunction "DTR_28") (pintype "bidirectional"))
    )
    (net (code "72") (name "unconnected-(IC11-NRST-Pad9)") (class "Default")
      (node (ref "IC11") (pin "9") (pinfunction "NRST_9") (pintype "bidirectional"))
    )
    (net (code "73") (name "unconnected-(IC11-NSUSPEND-Pad11)") (class "Default")
      (node (ref "IC11") (pin "11") (pinfunction "NSUSPEND_11") (pintype "bidirectional"))
    )
    (net (code "74") (name "unconnected-(IC11-RI-Pad2)") (class "Default")
      (node (ref "IC11") (pin "2") (pinfunction "RI_2") (pintype "bidirectional"))
    )
    (net (code "75") (name "unconnected-(IC11-RTS-Pad24)") (class "Default")
      (node (ref "IC11") (pin "24") (pinfunction "RTS_24") (pintype "bidirectional"))
    )
    (net (code "76") (name "unconnected-(IC11-SUSPEND-Pad12)") (class "Default")
      (node (ref "IC11") (pin "12") (pinfunction "SUSPEND_12") (pintype "bidirectional"))
    )
  )
)
